# -20210715.net
KiCad netlist of a schematic drawn in Altium Designer
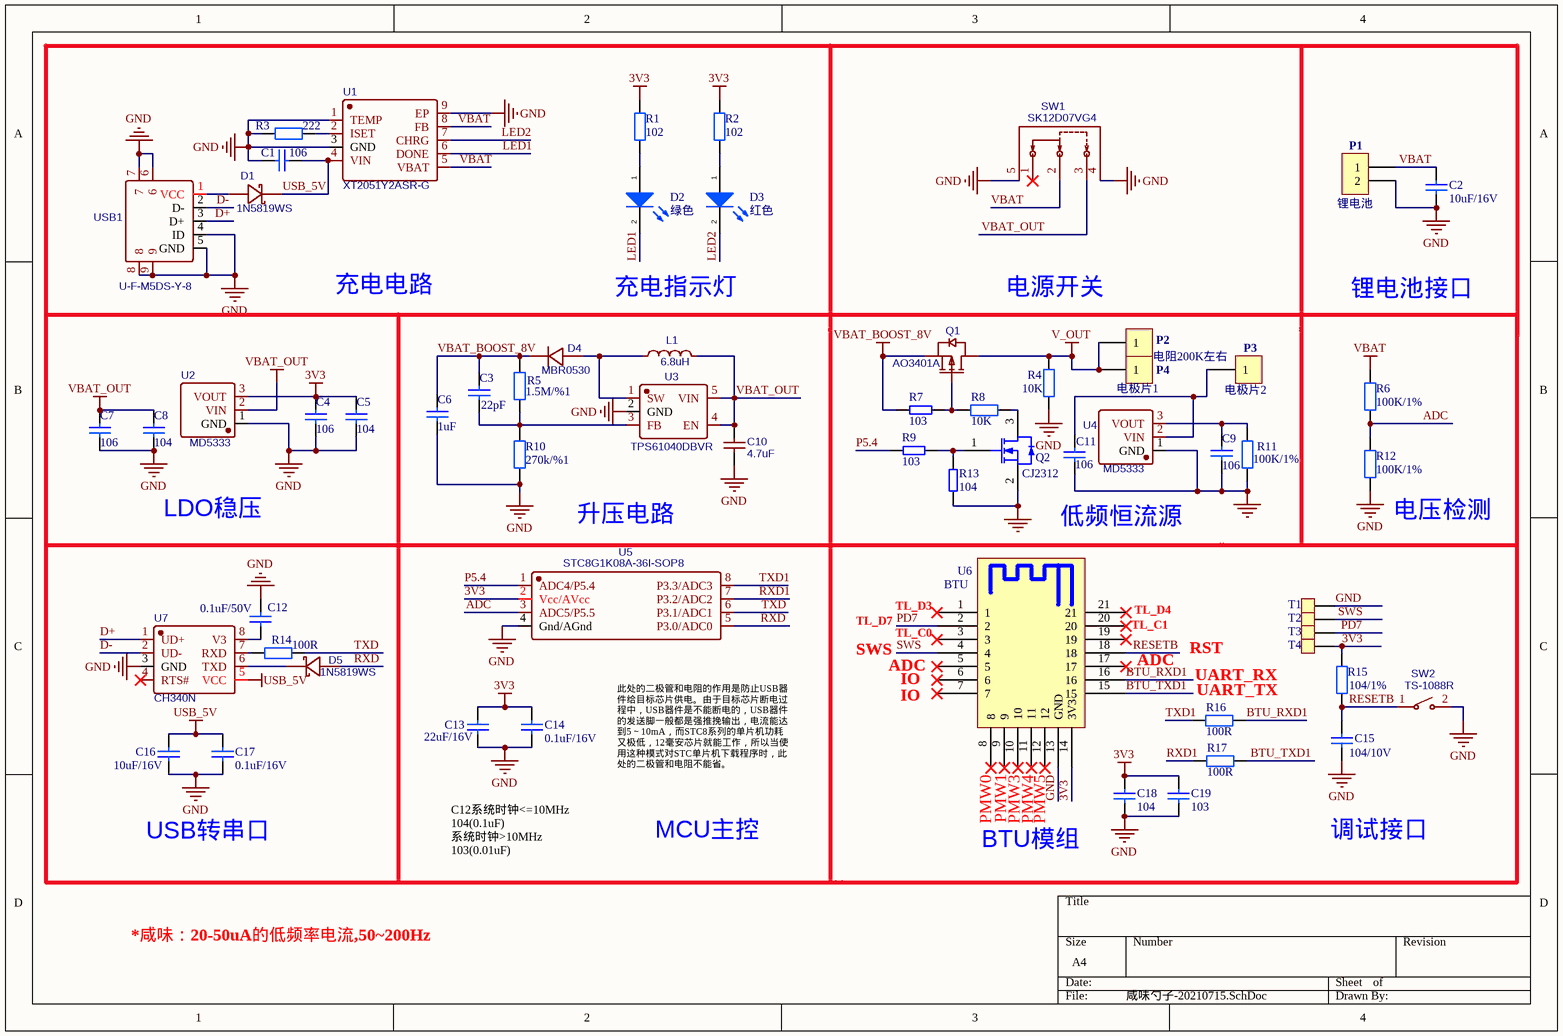
[diagram p0: 咸味勺子-20210715.SchDoc]

(export (version "E")
  (design (tool "Eeschema 10.0.6"))
  (components
    (comp (ref "C1")
      (value "106")
      (footprint "C0603")
      (description "无极性电容")
      (fields (field (name "PART NUMBER") "1.02.03.00181") (field (name "修改人") "system"))
      (libsource (lib "Database_Libs") (part "Capacitor - non polarized"))
    )
    (comp (ref "C2")
      (value "10uF/16V")
      (footprint "C0603")
      (description "无极性电容")
      (fields (field (name "PART NUMBER") "1.02.05.00869"))
      (libsource (lib "Database_Libs4") (part "Capacitor - non polarized"))
    )
    (comp (ref "C3")
      (value "22pF")
      (footprint "C0402_GRM15")
      (description "无极性电容")
      (fields (field (name "PART NUMBER") "1.02.05.00869"))
      (libsource (lib "Database_Libs4") (part "Capacitor - non polarized"))
    )
    (comp (ref "C4")
      (value "106")
      (footprint "C0603")
      (description "无极性电容")
      (fields (field (name "PART NUMBER") "1.02.05.00869"))
      (libsource (lib "Database_Libs4") (part "Capacitor - non polarized"))
    )
    (comp (ref "C5")
      (value "104")
      (footprint "C0402_GRM15")
      (description "无极性电容")
      (fields (field (name "PART NUMBER") "1.02.05.00869"))
      (libsource (lib "Database_Libs4") (part "Capacitor - non polarized"))
    )
    (comp (ref "C6")
      (value "1uF")
      (footprint "C0603")
      (description "无极性电容")
      (fields (field (name "PART NUMBER") "1.02.05.00869"))
      (libsource (lib "Database_Libs4") (part "Capacitor - non polarized"))
    )
    (comp (ref "C7")
      (value "106")
      (footprint "C0603")
      (description "无极性电容")
      (fields (field (name "PART NUMBER") "1.02.05.00869"))
      (libsource (lib "Database_Libs4") (part "Capacitor - non polarized"))
    )
    (comp (ref "C8")
      (value "104")
      (footprint "C0402_GRM15")
      (description "无极性电容")
      (fields (field (name "PART NUMBER") "1.02.05.00869"))
      (libsource (lib "Database_Libs4") (part "Capacitor - non polarized"))
    )
    (comp (ref "C9")
      (value "106")
      (footprint "C0603")
      (description "无极性电容")
      (fields (field (name "PART NUMBER") "1.02.05.00869"))
      (libsource (lib "Database_Libs4") (part "Capacitor - non polarized"))
    )
    (comp (ref "C10")
      (value "4.7uF")
      (footprint "JMK212BJ475KG-T")
      (fields
        (field (name "BOM_MANUFACTURER PART") "JMK212BJ475KG-T")
        (field (name "BOM_SUPPLIER PART") "C92788")
      )
      (libsource (lib "altium-import") (part "root_1_4.7uF_"))
    )
    (comp (ref "C11")
      (value "106")
      (footprint "C0603")
      (description "无极性电容")
      (fields (field (name "PART NUMBER") "1.02.05.00869"))
      (libsource (lib "Database_Libs4") (part "Capacitor - non polarized"))
    )
    (comp (ref "C12")
      (value "0.1uF/50V")
      (footprint "C0402_GRM15")
      (description "无极性电容")
      (fields (field (name "PART NUMBER") "1.02.05.00834") (field (name "修改人") "system"))
      (libsource (lib "Database_Libs") (part "Capacitor - non polarized"))
    )
    (comp (ref "C13")
      (value "22uF/16V")
      (footprint "C0603")
      (description "无极性电容")
      (fields (field (name "PART NUMBER") "1.02.03.00181") (field (name "修改人") "system"))
      (libsource (lib "Database_Libs") (part "Capacitor - non polarized"))
    )
    (comp (ref "C14")
      (value "0.1uF/16V")
      (footprint "C0402_GRM15")
      (description "无极性电容")
      (fields (field (name "PART NUMBER") "1.02.05.00834") (field (name "修改人") "system"))
      (libsource (lib "Database_Libs") (part "Capacitor - non polarized"))
    )
    (comp (ref "C15")
      (value "104/10V")
      (footprint "C0402_GRM15")
      (description "无极性电容")
      (fields (field (name "PART NUMBER") "1.02.05.00869"))
      (libsource (lib "Database_Libs4") (part "Capacitor - non polarized"))
    )
    (comp (ref "C16")
      (value "10uF/16V")
      (footprint "C0603")
      (description "无极性电容")
      (fields (field (name "PART NUMBER") "1.02.03.00181") (field (name "修改人") "system"))
      (libsource (lib "Database_Libs") (part "Capacitor - non polarized"))
    )
    (comp (ref "C17")
      (value "0.1uF/16V")
      (footprint "C0402_GRM15")
      (description "无极性电容")
      (fields (field (name "PART NUMBER") "1.02.05.00834") (field (name "修改人") "system"))
      (libsource (lib "Database_Libs") (part "Capacitor - non polarized"))
    )
    (comp (ref "C18")
      (value "104")
      (footprint "C0402_GRM15")
      (description "无极性电容")
      (fields (field (name "PART NUMBER") "1.02.05.00869"))
      (libsource (lib "Database_Libs4") (part "Capacitor - non polarized"))
    )
    (comp (ref "C19")
      (value "103")
      (footprint "C0402_GRM15")
      (description "无极性电容")
      (fields (field (name "PART NUMBER") "1.02.05.00869"))
      (libsource (lib "Database_Libs4") (part "Capacitor - non polarized"))
    )
    (comp (ref "D1")
      (value "1N5819WS")
      (footprint "1N5819WS")
      (fields (field (name "BOM_SUPPLIER PART") "C1884554") (field (name "CONTRIBUTOR") "LCSC"))
      (libsource (lib "altium-import") (part "root_2_1N5819WS_C1884554_"))
    )
    (comp (ref "D2")
      (value "绿色")
      (footprint "OSR50603C1E")
      (description "LED")
      (fields (field (name "PART NUMBER") "1.06.02.00452"))
      (libsource (lib "Database_Libs4") (part "LED"))
    )
    (comp (ref "D3")
      (value "红色")
      (footprint "OSR50603C1E")
      (description "LED")
      (fields (field (name "PART NUMBER") "1.06.02.00452"))
      (libsource (lib "Database_Libs4") (part "LED"))
    )
    (comp (ref "D4")
      (value "MBR0530")
      (footprint "MBR0530")
      (fields (field (name "BOM_SUPPLIER PART") "C475718") (field (name "CONTRIBUTOR") "LCSC"))
      (libsource (lib "altium-import") (part "root_0_MBR0530_C475718_"))
    )
    (comp (ref "D5")
      (value "1N5819WS")
      (footprint "1N5819WS")
      (fields (field (name "BOM_SUPPLIER PART") "C1884554") (field (name "CONTRIBUTOR") "LCSC"))
      (libsource (lib "altium-import") (part "root_0_1N5819WS_C1884554_"))
    )
    (comp (ref "L1")
      (value "6.8uH")
      (footprint "CDRH3D23NP-6R8PC")
      (fields
        (field (name "BOM_SUPPLIER PART") "C323532")
        (field (name "BOM_MANUFACTURER PART") "CDRH3D23NP-6R8PC")
        (field (name "CONTRIBUTOR") "LCSC")
      )
      (libsource (lib "altium-import") (part "root_0_6.8uH_"))
    )
    (comp (ref "P1")
      (value "锂电池")
      (footprint "1.5mm 2p接插件")
      (description "Connector")
      (libsource (lib "*") (part "CON2"))
    )
    (comp (ref "P2") (value "CON1") (footprint "焊点1") (libsource (lib "智能烧水壶 -电源板") (part "CON1")))
    (comp (ref "P3") (value "CON1") (footprint "焊点1") (libsource (lib "智能烧水壶 -电源板") (part "CON1")))
    (comp (ref "P4") (value "CON1") (footprint "焊点1") (libsource (lib "智能烧水壶 -电源板") (part "CON1")))
    (comp (ref "Q1")
      (value "AO3401A")
      (footprint "AO3401A")
      (fields (field (name "BOM_SUPPLIER PART") "C700954") (field (name "CONTRIBUTOR") "LCSC"))
      (libsource (lib "altium-import") (part "root_1_mirrored_AO3401A_C700954_"))
    )
    (comp (ref "Q2")
      (value "CJ2312")
      (footprint "CJ2312")
      (description "N-Channel MOSFET")
      (fields
        (field (name "PART NUMBER") "1.06.11.00008")
        (field (name "ORCAD LIBRARY PATH") "‪Z:\\tuya_lib\\sch-lib\\DISCRETE.OLB")
        (field (name "修改人") "system")
      )
      (libsource (lib "Database_Libs") (part "MOSFET-N"))
    )
    (comp (ref "R1")
      (value "102")
      (footprint "R0402")
      (description "电阻")
      (fields (field (name "PART NUMBER") "1.01.01.00808"))
      (libsource (lib "Database_Libs4") (part "Resistor"))
    )
    (comp (ref "R2")
      (value "102")
      (footprint "R0402")
      (description "电阻")
      (fields (field (name "PART NUMBER") "1.01.01.00808"))
      (libsource (lib "Database_Libs4") (part "Resistor"))
    )
    (comp (ref "R3")
      (value "222")
      (footprint "R0402")
      (description "电阻")
      (fields (field (name "PART NUMBER") "1.01.01.00808"))
      (libsource (lib "") (part "Resistor_1"))
    )
    (comp (ref "R4")
      (value "10K")
      (footprint "R0402")
      (description "电阻")
      (libsource (lib "") (part "Resistor_1"))
    )
    (comp (ref "R5")
      (value "1.5M/%1")
      (footprint "R0402")
      (description "电阻")
      (libsource (lib "Database_Libs") (part "Resistor"))
    )
    (comp (ref "R6")
      (value "100K/1%")
      (footprint "R0402")
      (description "电阻")
      (libsource (lib "Database_Libs") (part "Resistor"))
    )
    (comp (ref "R7")
      (value "103")
      (footprint "R0402")
      (description "RES")
      (libsource (lib "先锋器件封装库") (part "RES-1"))
    )
    (comp (ref "R8")
      (value "10K")
      (footprint "R0402")
      (description "电阻")
      (libsource (lib "") (part "Resistor_2"))
    )
    (comp (ref "R9")
      (value "103")
      (footprint "R0402")
      (description "RES")
      (libsource (lib "先锋器件封装库") (part "RES-1"))
    )
    (comp (ref "R10")
      (value "270k/%1")
      (footprint "R0402")
      (description "电阻")
      (libsource (lib "Database_Libs") (part "Resistor"))
    )
    (comp (ref "R11")
      (value "100K/1%")
      (footprint "R0402")
      (description "电阻")
      (libsource (lib "Database_Libs") (part "Resistor"))
    )
    (comp (ref "R12")
      (value "100K/1%")
      (footprint "R0402")
      (description "电阻")
      (libsource (lib "Database_Libs") (part "Resistor"))
    )
    (comp (ref "R13")
      (value "104")
      (footprint "R0402")
      (description "RES")
      (libsource (lib "先锋器件封装库") (part "RES-1"))
    )
    (comp (ref "R14")
      (value "100R")
      (footprint "R0402")
      (description "电阻")
      (fields (field (name "PART NUMBER") "1.01.01.00808") (field (name "修改人") "system"))
      (libsource (lib "") (part "Resistor_2"))
    )
    (comp (ref "R15")
      (value "104/1%")
      (footprint "R0402")
      (description "电阻")
      (fields (field (name "PART NUMBER") "1.01.01.00808"))
      (libsource (lib "Database_Libs4") (part "Resistor"))
    )
    (comp (ref "R16")
      (value "100R")
      (footprint "R0402")
      (description "电阻")
      (fields (field (name "PART NUMBER") "1.01.01.00808"))
      (libsource (lib "") (part "Resistor_1"))
    )
    (comp (ref "R17")
      (value "100R")
      (footprint "R0402")
      (description "电阻")
      (fields (field (name "PART NUMBER") "1.01.01.00808"))
      (libsource (lib "") (part "Resistor_1"))
    )
    (comp (ref "SW1")
      (value "SK12D07VG4")
      (footprint "SK12D07VG4")
      (fields (field (name "BOM_SUPPLIER PART") "C393937") (field (name "CONTRIBUTOR") "LCSC"))
      (libsource (lib "altium-import") (part "root_0_SK12D07VG4_"))
    )
    (comp (ref "SW2")
      (value "TS-1088R")
      (footprint "TS-1088R-02026")
      (fields
        (field (name "BOM_SUPPLIER PART") "C455280")
        (field (name "BOM_MANUFACTURER PART") "TS-1088R-02026")
        (field (name "CONTRIBUTOR") "LCSC")
      )
      (libsource (lib "altium-import") (part "root_0_TS-1088R-02026_"))
    )
    (comp (ref "T1") (value "TP") (footprint "TP1") (libsource (lib "MIAXIS-SCH") (part "TP")))
    (comp (ref "T2") (value "TP") (footprint "TP1") (libsource (lib "MIAXIS-SCH") (part "TP")))
    (comp (ref "T3") (value "TP") (footprint "TP1") (libsource (lib "MIAXIS-SCH") (part "TP")))
    (comp (ref "T4") (value "TP") (footprint "TP1") (libsource (lib "MIAXIS-SCH") (part "TP")))
    (comp (ref "U1")
      (value "XT2051Y2ASR-G")
      (footprint "XT2051Y2ASR-G")
      (fields (field (name "BOM_SUPPLIER PART") "C236398") (field (name "CONTRIBUTOR") "LCSC"))
      (libsource (lib "altium-import") (part "root_0_XT2051Y2ASR-G_"))
    )
    (comp (ref "U2")
      (value "MD5333")
      (footprint "MD5333")
      (fields (field (name "BOM_SUPPLIER PART") "C2827936") (field (name "CONTRIBUTOR") "LCSC"))
      (libsource (lib "altium-import") (part "root_2_MD5333_"))
    )
    (comp (ref "U3")
      (value "TPS61040DBVR")
      (footprint "TPS61040DBVR")
      (fields (field (name "BOM_SUPPLIER PART") "C7722"))
      (libsource (lib "altium-import") (part "root_0_TPS61040DBVR_"))
    )
    (comp (ref "U4")
      (value "MD5333")
      (footprint "MD5333")
      (fields (field (name "BOM_SUPPLIER PART") "C2827936") (field (name "CONTRIBUTOR") "LCSC"))
      (libsource (lib "altium-import") (part "root_2_MD5333_"))
    )
    (comp (ref "U5")
      (value "STC8G1K08A-36I-SOP8")
      (footprint "STC8G1K08A-36I-SOP8")
      (fields (field (name "BOM_SUPPLIER PART") "C915663") (field (name "CONTRIBUTOR") "LCSC"))
      (libsource (lib "altium-import") (part "root_0_STC8G1K08A-36I-SOP8_"))
    )
    (comp (ref "U6")
      (value "BTU")
      (footprint "CBU1")
      (fields (field (name "PART NUMBER") "0110"))
      (libsource (lib "BTU_V100") (part "CBU"))
    )
    (comp (ref "U7")
      (value "CH340N")
      (footprint "CH340N")
      (fields (field (name "BOM_SUPPLIER PART") "C506813") (field (name "CONTRIBUTOR") "LCSC"))
      (libsource (lib "TY") (part "CH340N"))
    )
    (comp (ref "USB1")
      (value "U-F-M5DS-Y-8")
      (footprint "U-F-M5DS-Y-8")
      (fields (field (name "BOM_SUPPLIER PART") "C961761") (field (name "CONTRIBUTOR") "LCSC"))
      (libsource (lib "altium-import") (part "root_0_U-F-M5DS-Y-8_"))
    )
  )
  (nets
    (net (code "1") (name "/ADC") (class "Default")
      (node (ref "R12") (pin "2") (pinfunction "2_2") (pintype "passive"))
      (node (ref "R6") (pin "1") (pinfunction "1_1") (pintype "passive"))
      (node (ref "U5") (pin "3") (pinfunction "ADC5/P5.5_3") (pintype "passive"))
    )
    (net (code "2") (name "/BTU_RXD1") (class "Default")
      (node (ref "R16") (pin "1") (pinfunction "1_1") (pintype "passive"))
      (node (ref "U6") (pin "16") (pinfunction "16_16") (pintype "passive"))
    )
    (net (code "3") (name "/BTU_TXD1") (class "Default")
      (node (ref "R17") (pin "1") (pinfunction "1_1") (pintype "passive"))
      (node (ref "U6") (pin "15") (pinfunction "15_15") (pintype "passive"))
    )
    (net (code "4") (name "/D+") (class "Default")
      (node (ref "U7") (pin "1") (pinfunction "UD+_1") (pintype "passive"))
      (node (ref "USB1") (pin "3") (pinfunction "D+_3") (pintype "passive"))
    )
    (net (code "5") (name "/D-") (class "Default")
      (node (ref "U7") (pin "2") (pinfunction "UD-_2") (pintype "passive"))
      (node (ref "USB1") (pin "2") (pinfunction "D-_2") (pintype "passive"))
    )
    (net (code "6") (name "/LED1") (class "Default")
      (node (ref "D2") (pin "2") (pinfunction "2_2") (pintype "passive"))
      (node (ref "U1") (pin "6") (pinfunction "DONE_6") (pintype "passive"))
    )
    (net (code "7") (name "/LED2") (class "Default")
      (node (ref "D3") (pin "2") (pinfunction "2_2") (pintype "passive"))
      (node (ref "U1") (pin "7") (pinfunction "CHRG_7") (pintype "passive"))
    )
    (net (code "8") (name "/P5.4") (class "Default")
      (node (ref "R9") (pin "1") (pintype "passive"))
      (node (ref "U5") (pin "1") (pinfunction "ADC4/P5.4_1") (pintype "passive"))
    )
    (net (code "9") (name "/PD7") (class "Default")
      (node (ref "T3") (pin "1") (pinfunction "1_1") (pintype "passive"))
      (node (ref "U6") (pin "2") (pinfunction "2_2") (pintype "passive"))
    )
    (net (code "10") (name "/RESETB") (class "Default")
      (node (ref "C15") (pin "1") (pinfunction "1_1") (pintype "passive"))
      (node (ref "R15") (pin "1") (pinfunction "1_1") (pintype "passive"))
      (node (ref "SW2") (pin "1") (pinfunction "1_1") (pintype "passive"))
      (node (ref "U6") (pin "18") (pinfunction "18_18") (pintype "passive"))
    )
    (net (code "11") (name "/RXD") (class "Default")
      (node (ref "D5") (pin "2") (pinfunction "A_2") (pintype "passive"))
      (node (ref "U5") (pin "5") (pinfunction "P3.0/ADC0_5") (pintype "passive"))
    )
    (net (code "12") (name "/RXD1") (class "Default")
      (node (ref "R17") (pin "2") (pinfunction "2_2") (pintype "passive"))
      (node (ref "U5") (pin "7") (pinfunction "P3.2/ADC2_7") (pintype "passive"))
    )
    (net (code "13") (name "/SWS") (class "Default")
      (node (ref "T2") (pin "1") (pinfunction "1_1") (pintype "passive"))
      (node (ref "U6") (pin "4") (pinfunction "4_4") (pintype "passive"))
    )
    (net (code "14") (name "/TXD") (class "Default")
      (node (ref "R14") (pin "2") (pinfunction "2_2") (pintype "passive"))
      (node (ref "U5") (pin "6") (pinfunction "P3.1/ADC1_6") (pintype "passive"))
    )
    (net (code "15") (name "/TXD1") (class "Default")
      (node (ref "R16") (pin "2") (pinfunction "2_2") (pintype "passive"))
      (node (ref "U5") (pin "8") (pinfunction "P3.3/ADC3_8") (pintype "passive"))
    )
    (net (code "16") (name "3V3") (class "Default")
      (node (ref "C13") (pin "2") (pinfunction "2_2") (pintype "passive"))
      (node (ref "C14") (pin "2") (pinfunction "2_2") (pintype "passive"))
      (node (ref "C18") (pin "1") (pinfunction "1_1") (pintype "passive"))
      (node (ref "C19") (pin "1") (pinfunction "1_1") (pintype "passive"))
      (node (ref "C4") (pin "1") (pinfunction "1_1") (pintype "passive"))
      (node (ref "C5") (pin "1") (pinfunction "1_1") (pintype "passive"))
      (node (ref "R1") (pin "2") (pinfunction "2_2") (pintype "passive"))
      (node (ref "R15") (pin "2") (pinfunction "2_2") (pintype "passive"))
      (node (ref "R2") (pin "2") (pinfunction "2_2") (pintype "passive"))
      (node (ref "T4") (pin "1") (pinfunction "1_1") (pintype "passive"))
      (node (ref "U2") (pin "3") (pinfunction "VOUT_3") (pintype "passive"))
      (node (ref "U5") (pin "2") (pinfunction "Vcc/AVcc_2") (pintype "passive"))
      (node (ref "U6") (pin "14") (pinfunction "3V3_14") (pintype "passive"))
    )
    (net (code "17") (name "GND") (class "Default")
      (node (ref "C1") (pin "2") (pinfunction "2_2") (pintype "passive"))
      (node (ref "C10") (pin "1") (pinfunction "1_1") (pintype "passive"))
      (node (ref "C11") (pin "2") (pinfunction "2_2") (pintype "passive"))
      (node (ref "C12") (pin "2") (pinfunction "2_2") (pintype "passive"))
      (node (ref "C13") (pin "1") (pinfunction "1_1") (pintype "passive"))
      (node (ref "C14") (pin "1") (pinfunction "1_1") (pintype "passive"))
      (node (ref "C15") (pin "2") (pinfunction "2_2") (pintype "passive"))
      (node (ref "C16") (pin "1") (pinfunction "1_1") (pintype "passive"))
      (node (ref "C17") (pin "1") (pinfunction "1_1") (pintype "passive"))
      (node (ref "C18") (pin "2") (pinfunction "2_2") (pintype "passive"))
      (node (ref "C19") (pin "2") (pinfunction "2_2") (pintype "passive"))
      (node (ref "C2") (pin "2") (pinfunction "2_2") (pintype "passive"))
      (node (ref "C4") (pin "2") (pinfunction "2_2") (pintype "passive"))
      (node (ref "C5") (pin "2") (pinfunction "2_2") (pintype "passive"))
      (node (ref "C6") (pin "2") (pinfunction "2_2") (pintype "passive"))
      (node (ref "C7") (pin "2") (pinfunction "2_2") (pintype "passive"))
      (node (ref "C8") (pin "2") (pinfunction "2_2") (pintype "passive"))
      (node (ref "C9") (pin "2") (pinfunction "2_2") (pintype "passive"))
      (node (ref "P1") (pin "2") (pinfunction "2_2") (pintype "passive"))
      (node (ref "Q2") (pin "2") (pinfunction "S_2") (pintype "passive"))
      (node (ref "R10") (pin "1") (pinfunction "1_1") (pintype "passive"))
      (node (ref "R11") (pin "1") (pinfunction "1_1") (pintype "passive"))
      (node (ref "R12") (pin "1") (pinfunction "1_1") (pintype "passive"))
      (node (ref "R13") (pin "1") (pintype "passive"))
      (node (ref "R3") (pin "2") (pinfunction "2_2") (pintype "passive"))
      (node (ref "R4") (pin "2") (pinfunction "2_2") (pintype "passive"))
      (node (ref "SW1") (pin "4") (pinfunction "4_4") (pintype "passive"))
      (node (ref "SW1") (pin "5") (pinfunction "5_5") (pintype "passive"))
      (node (ref "SW2") (pin "2") (pinfunction "2_2") (pintype "passive"))
      (node (ref "T1") (pin "1") (pinfunction "1_1") (pintype "passive"))
      (node (ref "U1") (pin "1") (pinfunction "TEMP_1") (pintype "passive"))
      (node (ref "U1") (pin "3") (pinfunction "GND_3") (pintype "passive"))
      (node (ref "U1") (pin "9") (pinfunction "EP_9") (pintype "passive"))
      (node (ref "U2") (pin "1") (pinfunction "GND_1") (pintype "passive"))
      (node (ref "U3") (pin "2") (pinfunction "GND_2") (pintype "passive"))
      (node (ref "U4") (pin "1") (pinfunction "GND_1") (pintype "passive"))
      (node (ref "U5") (pin "4") (pinfunction "Gnd/AGnd_4") (pintype "passive"))
      (node (ref "U6") (pin "13") (pinfunction "GND_13") (pintype "passive"))
      (node (ref "U7") (pin "3") (pinfunction "GND_3") (pintype "passive"))
      (node (ref "USB1") (pin "4") (pinfunction "ID_4") (pintype "passive"))
      (node (ref "USB1") (pin "5") (pinfunction "GND_5") (pintype "passive"))
      (node (ref "USB1") (pin "6") (pinfunction "6_6") (pintype "passive"))
      (node (ref "USB1") (pin "7") (pinfunction "7_7") (pintype "passive"))
      (node (ref "USB1") (pin "8") (pinfunction "8_8") (pintype "passive"))
      (node (ref "USB1") (pin "9") (pinfunction "9_9") (pintype "passive"))
    )
    (net (code "18") (name "Net-(D1-A)") (class "Default")
      (node (ref "D1") (pin "2") (pinfunction "A_2") (pintype "passive"))
      (node (ref "USB1") (pin "1") (pinfunction "VCC_1") (pintype "passive"))
    )
    (net (code "19") (name "Net-(D2-Pad1)") (class "Default")
      (node (ref "D2") (pin "1") (pinfunction "1_1") (pintype "passive"))
      (node (ref "R1") (pin "1") (pinfunction "1_1") (pintype "passive"))
    )
    (net (code "20") (name "Net-(D3-Pad1)") (class "Default")
      (node (ref "D3") (pin "1") (pinfunction "1_1") (pintype "passive"))
      (node (ref "R2") (pin "1") (pinfunction "1_1") (pintype "passive"))
    )
    (net (code "21") (name "Net-(D4-A)") (class "Default")
      (node (ref "D4") (pin "2") (pinfunction "A_2") (pintype "passive"))
      (node (ref "L1") (pin "1") (pinfunction "1_1") (pintype "passive"))
      (node (ref "U3") (pin "1") (pinfunction "SW_1") (pintype "passive"))
    )
    (net (code "22") (name "Net-(D5-C)") (class "Default")
      (node (ref "D5") (pin "1") (pinfunction "C_1") (pintype "passive"))
      (node (ref "U7") (pin "6") (pinfunction "TXD_6") (pintype "passive"))
    )
    (net (code "23") (name "Net-(Q1-G)") (class "Default")
      (node (ref "Q1") (pin "1") (pinfunction "G_1") (pintype "passive"))
      (node (ref "R7") (pin "2") (pintype "passive"))
      (node (ref "R8") (pin "1") (pinfunction "1_1") (pintype "passive"))
    )
    (net (code "24") (name "Net-(Q2-D)") (class "Default")
      (node (ref "Q2") (pin "3") (pinfunction "D_3") (pintype "passive"))
      (node (ref "R8") (pin "2") (pinfunction "2_2") (pintype "passive"))
    )
    (net (code "25") (name "Net-(Q2-G)") (class "Default")
      (node (ref "Q2") (pin "1") (pinfunction "G_1") (pintype "passive"))
      (node (ref "R13") (pin "2") (pintype "passive"))
      (node (ref "R9") (pin "2") (pintype "passive"))
    )
    (net (code "26") (name "Net-(U1-ISET)") (class "Default")
      (node (ref "R3") (pin "1") (pinfunction "1_1") (pintype "passive"))
      (node (ref "U1") (pin "2") (pinfunction "ISET_2") (pintype "passive"))
    )
    (net (code "27") (name "Net-(U3-FB)") (class "Default")
      (node (ref "C3") (pin "2") (pinfunction "2_2") (pintype "passive"))
      (node (ref "R10") (pin "2") (pinfunction "2_2") (pintype "passive"))
      (node (ref "R5") (pin "1") (pinfunction "1_1") (pintype "passive"))
      (node (ref "U3") (pin "3") (pinfunction "FB_3") (pintype "passive"))
    )
    (net (code "28") (name "Net-(U4-VIN)") (class "Default")
      (node (ref "C11") (pin "1") (pinfunction "1_1") (pintype "passive"))
      (node (ref "P3") (pin "1") (pinfunction "1_1") (pintype "passive"))
      (node (ref "U4") (pin "2") (pinfunction "VIN_2") (pintype "passive"))
    )
    (net (code "29") (name "Net-(U4-VOUT)") (class "Default")
      (node (ref "C9") (pin "1") (pinfunction "1_1") (pintype "passive"))
      (node (ref "R11") (pin "2") (pinfunction "2_2") (pintype "passive"))
      (node (ref "U4") (pin "3") (pinfunction "VOUT_3") (pintype "passive"))
    )
    (net (code "30") (name "Net-(U7-RXD)") (class "Default")
      (node (ref "R14") (pin "1") (pinfunction "1_1") (pintype "passive"))
      (node (ref "U7") (pin "7") (pinfunction "RXD_7") (pintype "passive"))
    )
    (net (code "31") (name "Net-(U7-V3)") (class "Default")
      (node (ref "C12") (pin "1") (pinfunction "1_1") (pintype "passive"))
      (node (ref "U7") (pin "8") (pinfunction "V3_8") (pintype "passive"))
    )
    (net (code "32") (name "USB_5V") (class "Default")
      (node (ref "C1") (pin "1") (pinfunction "1_1") (pintype "passive"))
      (node (ref "C16") (pin "2") (pinfunction "2_2") (pintype "passive"))
      (node (ref "C17") (pin "2") (pinfunction "2_2") (pintype "passive"))
      (node (ref "D1") (pin "1") (pinfunction "C_1") (pintype "passive"))
      (node (ref "U1") (pin "4") (pinfunction "VIN_4") (pintype "passive"))
      (node (ref "U7") (pin "5") (pinfunction "VCC_5") (pintype "passive"))
    )
    (net (code "33") (name "VBAT") (class "Default")
      (node (ref "C2") (pin "1") (pinfunction "1_1") (pintype "passive"))
      (node (ref "P1") (pin "1") (pinfunction "1_1") (pintype "passive"))
      (node (ref "R6") (pin "2") (pinfunction "2_2") (pintype "passive"))
      (node (ref "SW1") (pin "2") (pinfunction "2_2") (pintype "passive"))
      (node (ref "U1") (pin "5") (pinfunction "VBAT_5") (pintype "passive"))
      (node (ref "U1") (pin "8") (pinfunction "FB_8") (pintype "passive"))
    )
    (net (code "34") (name "VBAT_BOOST_8V") (class "Default")
      (node (ref "C3") (pin "1") (pinfunction "1_1") (pintype "passive"))
      (node (ref "C6") (pin "1") (pinfunction "1_1") (pintype "passive"))
      (node (ref "D4") (pin "1") (pinfunction "K_1") (pintype "passive"))
      (node (ref "Q1") (pin "2") (pinfunction "S_2") (pintype "passive"))
      (node (ref "R5") (pin "2") (pinfunction "2_2") (pintype "passive"))
      (node (ref "R7") (pin "1") (pintype "passive"))
    )
    (net (code "35") (name "VBAT_OUT") (class "Default")
      (node (ref "C10") (pin "2") (pinfunction "2_2") (pintype "passive"))
      (node (ref "C7") (pin "1") (pinfunction "1_1") (pintype "passive"))
      (node (ref "C8") (pin "1") (pinfunction "1_1") (pintype "passive"))
      (node (ref "L1") (pin "2") (pinfunction "2_2") (pintype "passive"))
      (node (ref "SW1") (pin "3") (pinfunction "3_3") (pintype "passive"))
      (node (ref "U2") (pin "2") (pinfunction "VIN_2") (pintype "passive"))
      (node (ref "U3") (pin "4") (pinfunction "EN_4") (pintype "passive"))
      (node (ref "U3") (pin "5") (pinfunction "VIN_5") (pintype "passive"))
    )
    (net (code "36") (name "V_OUT") (class "Default")
      (node (ref "P2") (pin "1") (pinfunction "1_1") (pintype "passive"))
      (node (ref "P4") (pin "1") (pinfunction "1_1") (pintype "passive"))
      (node (ref "Q1") (pin "3") (pinfunction "D_3") (pintype "passive"))
      (node (ref "R4") (pin "1") (pinfunction "1_1") (pintype "passive"))
    )
    (net (code "37") (name "unconnected-(SW1-Pad1)") (class "Default")
      (node (ref "SW1") (pin "1") (pinfunction "1_1") (pintype "passive+no_connect"))
    )
    (net (code "38") (name "unconnected-(U6-Pad1)") (class "Default")
      (node (ref "U6") (pin "1") (pinfunction "1_1") (pintype "passive+no_connect"))
    )
    (net (code "39") (name "unconnected-(U6-Pad3)") (class "Default")
      (node (ref "U6") (pin "3") (pinfunction "3_3") (pintype "passive+no_connect"))
    )
    (net (code "40") (name "unconnected-(U6-Pad5)") (class "Default")
      (node (ref "U6") (pin "5") (pinfunction "5_5") (pintype "passive+no_connect"))
    )
    (net (code "41") (name "unconnected-(U6-Pad6)") (class "Default")
      (node (ref "U6") (pin "6") (pinfunction "6_6") (pintype "passive+no_connect"))
    )
    (net (code "42") (name "unconnected-(U6-Pad7)") (class "Default")
      (node (ref "U6") (pin "7") (pinfunction "7_7") (pintype "passive+no_connect"))
    )
    (net (code "43") (name "unconnected-(U6-Pad8)") (class "Default")
      (node (ref "U6") (pin "8") (pinfunction "8_8") (pintype "passive+no_connect"))
    )
    (net (code "44") (name "unconnected-(U6-Pad9)") (class "Default")
      (node (ref "U6") (pin "9") (pinfunction "9_9") (pintype "passive+no_connect"))
    )
    (net (code "45") (name "unconnected-(U6-Pad10)") (class "Default")
      (node (ref "U6") (pin "10") (pinfunction "10_10") (pintype "passive+no_connect"))
    )
    (net (code "46") (name "unconnected-(U6-Pad11)") (class "Default")
      (node (ref "U6") (pin "11") (pinfunction "11_11") (pintype "passive+no_connect"))
    )
    (net (code "47") (name "unconnected-(U6-Pad12)") (class "Default")
      (node (ref "U6") (pin "12") (pinfunction "12_12") (pintype "passive+no_connect"))
    )
    (net (code "48") (name "unconnected-(U6-Pad17)") (class "Default")
      (node (ref "U6") (pin "17") (pinfunction "17_17") (pintype "passive+no_connect"))
    )
    (net (code "49") (name "unconnected-(U6-Pad19)") (class "Default")
      (node (ref "U6") (pin "19") (pinfunction "19_19") (pintype "passive+no_connect"))
    )
    (net (code "50") (name "unconnected-(U6-Pad20)") (class "Default")
      (node (ref "U6") (pin "20") (pinfunction "20_20") (pintype "passive+no_connect"))
    )
    (net (code "51") (name "unconnected-(U6-Pad21)") (class "Default")
      (node (ref "U6") (pin "21") (pinfunction "21_21") (pintype "passive+no_connect"))
    )
    (net (code "52") (name "unconnected-(U7-RTS#-Pad4)") (class "Default")
      (node (ref "U7") (pin "4") (pinfunction "RTS#_4") (pintype "passive+no_connect"))
    )
  )
)
